# LCM_Dimmer.net
KiCad netlist of a schematic drawn in EAGLE
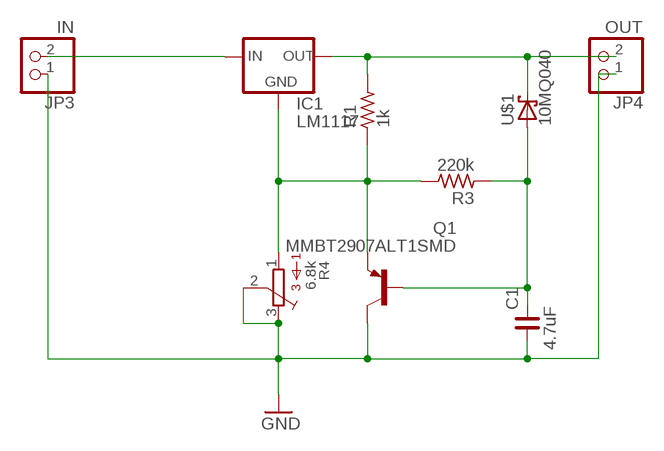
[diagram p0: schematic, sheet 1]

(export (version "E")
  (design (tool "Eeschema 10.0.6"))
  (components
    (comp (ref "C1")
      (value "4.7uF")
      (footprint "eagle-import:C1206")
      (libsource (lib "eagle-import") (part "C_1206"))
    )
    (comp (ref "IC1")
      (value "LM1117")
      (footprint "eagle-import:SOT223")
      (libsource (lib "eagle-import") (part "LM1117"))
    )
    (comp (ref "JP3")
      (value "IN")
      (footprint "eagle-import:1X02-S")
      (libsource (lib "eagle-import") (part "PINHD-1X02_2.54-S"))
    )
    (comp (ref "JP4")
      (value "OUT")
      (footprint "eagle-import:1X02-S")
      (libsource (lib "eagle-import") (part "PINHD-1X02_2.54-S"))
    )
    (comp (ref "Q1")
      (value "MMBT2907ALT1SMD")
      (footprint "eagle-import:SOT23-BEC")
      (libsource (lib "eagle-import") (part "MMBT2907SMDALT1"))
    )
    (comp (ref "R1")
      (value "1k")
      (footprint "eagle-import:R1206")
      (libsource (lib "eagle-import") (part "R_1206"))
    )
    (comp (ref "R3")
      (value "220k")
      (footprint "eagle-import:R1206")
      (libsource (lib "eagle-import") (part "R_1206"))
    )
    (comp (ref "R4")
      (value "6.8k")
      (footprint "eagle-import:3362P")
      (libsource (lib "eagle-import") (part "3362P"))
    )
    (comp (ref "U$1")
      (value "10MQ040")
      (footprint "eagle-import:SMA")
      (libsource (lib "eagle-import") (part "10MQ040"))
    )
  )
  (nets
    (net (code "1") (name "GND") (class "Default")
      (node (ref "C1") (pin "1") (pinfunction "1_1") (pintype "passive"))
      (node (ref "JP3") (pin "1") (pinfunction "1_1") (pintype "passive"))
      (node (ref "JP4") (pin "1") (pinfunction "1_1") (pintype "passive"))
      (node (ref "Q1") (pin "C") (pinfunction "C_C") (pintype "passive"))
      (node (ref "R4") (pin "2") (pinfunction "2_2") (pintype "passive"))
      (node (ref "R4") (pin "3") (pinfunction "3_3") (pintype "passive"))
    )
    (net (code "2") (name "Net-(C1-Pad2)") (class "Default")
      (node (ref "C1") (pin "2") (pinfunction "2_2") (pintype "passive"))
      (node (ref "Q1") (pin "B") (pinfunction "B_B") (pintype "passive"))
      (node (ref "R3") (pin "1") (pinfunction "1_1") (pintype "passive"))
      (node (ref "U$1") (pin "A") (pinfunction "A_A") (pintype "passive"))
    )
    (net (code "3") (name "Net-(IC1-GND)") (class "Default")
      (node (ref "IC1") (pin "1") (pinfunction "GND_1") (pintype "input"))
      (node (ref "Q1") (pin "E") (pinfunction "E_E") (pintype "passive"))
      (node (ref "R1") (pin "1") (pinfunction "1_1") (pintype "passive"))
      (node (ref "R3") (pin "2") (pinfunction "2_2") (pintype "passive"))
      (node (ref "R4") (pin "1") (pinfunction "1_1") (pintype "passive"))
    )
    (net (code "4") (name "Net-(IC1-IN)") (class "Default")
      (node (ref "IC1") (pin "3") (pinfunction "IN_3") (pintype "input"))
      (node (ref "JP3") (pin "2") (pinfunction "2_2") (pintype "passive"))
    )
    (net (code "5") (name "Net-(IC1-OUT)") (class "Default")
      (node (ref "IC1") (pin "2") (pinfunction "OUT_2") (pintype "passive"))
      (node (ref "JP4") (pin "2") (pinfunction "2_2") (pintype "passive"))
      (node (ref "R1") (pin "2") (pinfunction "2_2") (pintype "passive"))
      (node (ref "U$1") (pin "C") (pinfunction "C_C") (pintype "passive"))
    )
  )
)
